# Sorter.net
KiCad netlist of a schematic drawn in EAGLE
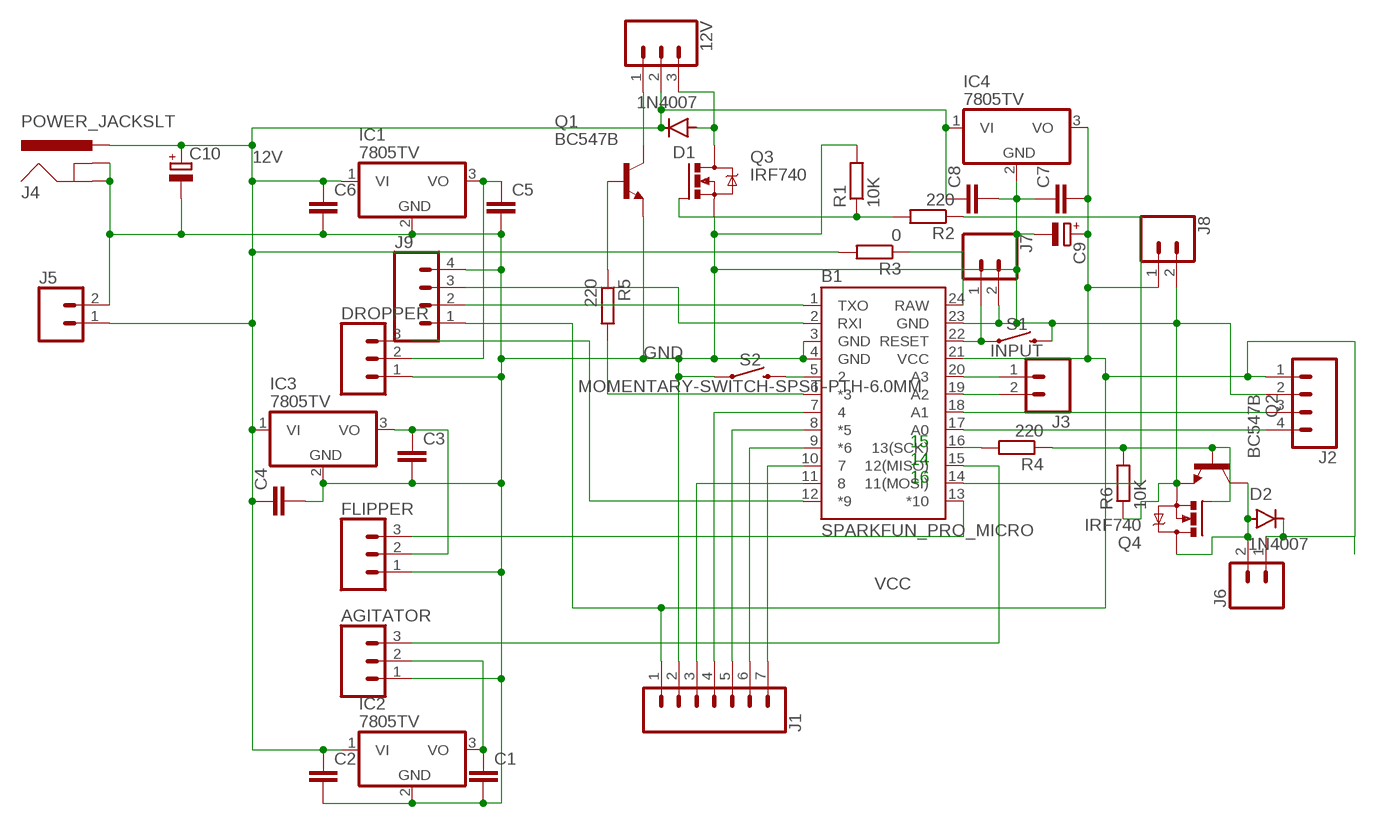
[diagram p0: schematic, sheet 1]

(export (version "E")
  (design (tool "Eeschema 10.0.6"))
  (components
    (comp (ref "12V")
      (value "CONN_03LONGPADS")
      (footprint "eagle-import:1X03_LONGPADS")
      (libsource (lib "eagle-import") (part "CONN_03LONGPADS"))
    )
    (comp (ref "AGITATOR")
      (value "CONN_03LONGPADS")
      (footprint "eagle-import:1X03_LONGPADS")
      (libsource (lib "eagle-import") (part "CONN_03LONGPADS"))
    )
    (comp (ref "B1")
      (value "SPARKFUN_PRO_MICRO")
      (footprint "eagle-import:SPARKFUN_PRO_MICRO")
      (libsource (lib "eagle-import") (part "SPARKFUN_PRO_MICRO"))
    )
    (comp (ref "C1")
      (value "C2.5/2")
      (footprint "eagle-import:C2.5-2")
      (libsource (lib "eagle-import") (part "C2.5/2"))
    )
    (comp (ref "C2")
      (value "C2.5/2")
      (footprint "eagle-import:C2.5-2")
      (libsource (lib "eagle-import") (part "C2.5/2"))
    )
    (comp (ref "C3")
      (value "C2.5/2")
      (footprint "eagle-import:C2.5-2")
      (libsource (lib "eagle-import") (part "C2.5/2"))
    )
    (comp (ref "C4")
      (value "C2.5/2")
      (footprint "eagle-import:C2.5-2")
      (libsource (lib "eagle-import") (part "C2.5/2"))
    )
    (comp (ref "C5")
      (value "C2.5/2")
      (footprint "eagle-import:C2.5-2")
      (libsource (lib "eagle-import") (part "C2.5/2"))
    )
    (comp (ref "C6")
      (value "C2.5/2")
      (footprint "eagle-import:C2.5-2")
      (libsource (lib "eagle-import") (part "C2.5/2"))
    )
    (comp (ref "C7")
      (value "C2.5/2")
      (footprint "eagle-import:C2.5-2")
      (libsource (lib "eagle-import") (part "C2.5/2"))
    )
    (comp (ref "C8")
      (value "C2.5/2")
      (footprint "eagle-import:C2.5-2")
      (libsource (lib "eagle-import") (part "C2.5/2"))
    )
    (comp (ref "C9")
      (value "CPOL-EUE2.5-5")
      (footprint "eagle-import:E2,5-5")
      (libsource (lib "eagle-import") (part "CPOL-EUE2.5-5"))
    )
    (comp (ref "C10")
      (value "CPOL-EUE2.5-5")
      (footprint "eagle-import:E2,5-5")
      (libsource (lib "eagle-import") (part "CPOL-EUE2.5-5"))
    )
    (comp (ref "D1")
      (value "1N4007")
      (footprint "eagle-import:DO-41")
      (fields
        (field (name "DIGIKEY_PART_NUMBER") "1N4007MSCT-ND")
        (field (name "MANUFACTURER") "Micro Commercial Co")
        (field (name "CREATED_BY") "PCBLayout.com")
      )
      (libsource (lib "eagle-import") (part "1N4007"))
    )
    (comp (ref "D2")
      (value "1N4007")
      (footprint "eagle-import:DO-41")
      (fields
        (field (name "DIGIKEY_PART_NUMBER") "1N4007MSCT-ND")
        (field (name "MANUFACTURER") "Micro Commercial Co")
        (field (name "CREATED_BY") "PCBLayout.com")
      )
      (libsource (lib "eagle-import") (part "1N4007"))
    )
    (comp (ref "DROPPER")
      (value "CONN_03LONGPADS")
      (footprint "eagle-import:1X03_LONGPADS")
      (libsource (lib "eagle-import") (part "CONN_03LONGPADS"))
    )
    (comp (ref "FLIPPER")
      (value "CONN_03LONGPADS")
      (footprint "eagle-import:1X03_LONGPADS")
      (libsource (lib "eagle-import") (part "CONN_03LONGPADS"))
    )
    (comp (ref "IC1")
      (value "7805TV")
      (footprint "eagle-import:TO220V")
      (libsource (lib "eagle-import") (part "78TV05"))
    )
    (comp (ref "IC2")
      (value "7805TV")
      (footprint "eagle-import:TO220V")
      (libsource (lib "eagle-import") (part "78TV05"))
    )
    (comp (ref "IC3")
      (value "7805TV")
      (footprint "eagle-import:TO220V")
      (libsource (lib "eagle-import") (part "78TV05"))
    )
    (comp (ref "IC4")
      (value "7805TV")
      (footprint "eagle-import:TO220V")
      (libsource (lib "eagle-import") (part "78TV05"))
    )
    (comp (ref "J1")
      (value "CONN_07LONGPADS")
      (footprint "eagle-import:1X07_LONGPADS")
      (libsource (lib "eagle-import") (part "CONN_07LONGPADS"))
    )
    (comp (ref "J2")
      (value "CONN_04LONGPADS")
      (footprint "eagle-import:1X04_LONGPADS")
      (libsource (lib "eagle-import") (part "CONN_04LONGPADS"))
    )
    (comp (ref "J3")
      (value "CONN_02")
      (footprint "eagle-import:1X02")
      (libsource (lib "eagle-import") (part "CONN_02"))
    )
    (comp (ref "J4")
      (value "POWER_JACKSLT")
      (footprint "eagle-import:POWER_JACK_SLOT")
      (libsource (lib "eagle-import") (part "POWER_JACKSLT"))
    )
    (comp (ref "J5")
      (value "CONN_023.5MM")
      (footprint "eagle-import:SCREWTERMINAL-3.5MM-2")
      (libsource (lib "eagle-import") (part "CONN_023.5MM"))
    )
    (comp (ref "J6")
      (value "CONN_02PTH3")
      (footprint "eagle-import:1X02_LONGPADS")
      (libsource (lib "eagle-import") (part "CONN_02PTH3"))
    )
    (comp (ref "J7")
      (value "CONN_02PTH3")
      (footprint "eagle-import:1X02_LONGPADS")
      (libsource (lib "eagle-import") (part "CONN_02PTH3"))
    )
    (comp (ref "J8")
      (value "CONN_02")
      (footprint "eagle-import:1X02")
      (libsource (lib "eagle-import") (part "CONN_02"))
    )
    (comp (ref "J9")
      (value "CONN_04")
      (footprint "eagle-import:1X04")
      (libsource (lib "eagle-import") (part "CONN_04"))
    )
    (comp (ref "Q1")
      (value "BC547B")
      (footprint "eagle-import:TO92")
      (libsource (lib "eagle-import") (part "BC547B"))
    )
    (comp (ref "Q2")
      (value "BC547B")
      (footprint "eagle-import:TO92")
      (libsource (lib "eagle-import") (part "BC547B"))
    )
    (comp (ref "Q3")
      (value "IRF740")
      (footprint "eagle-import:TO220BV")
      (libsource (lib "eagle-import") (part "IRF740"))
    )
    (comp (ref "Q4")
      (value "IRF740")
      (footprint "eagle-import:TO220BV")
      (libsource (lib "eagle-import") (part "IRF740"))
    )
    (comp (ref "R1")
      (value "10K")
      (footprint "eagle-import:0204_7")
      (libsource (lib "eagle-import") (part "R-EU_0204/7"))
    )
    (comp (ref "R2")
      (value "220")
      (footprint "eagle-import:0204_7")
      (libsource (lib "eagle-import") (part "R-EU_0204/7"))
    )
    (comp (ref "R3")
      (value "0")
      (footprint "eagle-import:0204_7")
      (libsource (lib "eagle-import") (part "R-EU_0204/7"))
    )
    (comp (ref "R4")
      (value "220")
      (footprint "eagle-import:0204_7")
      (libsource (lib "eagle-import") (part "R-EU_0204/7"))
    )
    (comp (ref "R5")
      (value "220")
      (footprint "eagle-import:0204_7")
      (libsource (lib "eagle-import") (part "R-EU_0204/7"))
    )
    (comp (ref "R6")
      (value "10K")
      (footprint "eagle-import:0204_7")
      (libsource (lib "eagle-import") (part "R-EU_0204/7"))
    )
    (comp (ref "S1")
      (value "INPUT")
      (footprint "eagle-import:TACTILE_SWITCH_PTH_6.0MM")
      (libsource (lib "eagle-import") (part "MOMENTARY-SWITCH-SPST-PTH-6.0MM"))
    )
    (comp (ref "S2")
      (value "MOMENTARY-SWITCH-SPST-PTH-6.0MM")
      (footprint "eagle-import:TACTILE_SWITCH_PTH_6.0MM")
      (libsource (lib "eagle-import") (part "MOMENTARY-SWITCH-SPST-PTH-6.0MM"))
    )
  )
  (nets
    (net (code "1") (name "/12V") (class "Default")
      (node (ref "12V") (pin "2") (pinfunction "2_2") (pintype "passive"))
      (node (ref "C10") (pin "+") (pinfunction "+_+") (pintype "passive"))
      (node (ref "C2") (pin "1") (pinfunction "1_1") (pintype "passive"))
      (node (ref "C4") (pin "1") (pinfunction "1_1") (pintype "passive"))
      (node (ref "C6") (pin "1") (pinfunction "1_1") (pintype "passive"))
      (node (ref "C8") (pin "1") (pinfunction "1_1") (pintype "passive"))
      (node (ref "D1") (pin "C") (pinfunction "C_C") (pintype "passive"))
      (node (ref "IC1") (pin "1") (pinfunction "VI_1") (pintype "input"))
      (node (ref "IC2") (pin "1") (pinfunction "VI_1") (pintype "input"))
      (node (ref "IC3") (pin "1") (pinfunction "VI_1") (pintype "input"))
      (node (ref "IC4") (pin "1") (pinfunction "VI_1") (pintype "input"))
      (node (ref "J4") (pin "PWR") (pinfunction "PWR_PWR") (pintype "bidirectional"))
      (node (ref "J5") (pin "1") (pinfunction "1_1") (pintype "passive"))
      (node (ref "R3") (pin "2") (pinfunction "2_2") (pintype "passive"))
    )
    (net (code "2") (name "/GND") (class "Default")
      (node (ref "AGITATOR") (pin "1") (pinfunction "1_1") (pintype "passive"))
      (node (ref "B1") (pin "23") (pinfunction "GND_23") (pintype "power_in"))
      (node (ref "B1") (pin "3") (pinfunction "GND_3") (pintype "power_in"))
      (node (ref "B1") (pin "4") (pinfunction "GND_4") (pintype "power_in"))
      (node (ref "C1") (pin "2") (pinfunction "2_2") (pintype "passive"))
      (node (ref "C10") (pin "-") (pinfunction "-_-") (pintype "passive"))
      (node (ref "C2") (pin "2") (pinfunction "2_2") (pintype "passive"))
      (node (ref "C3") (pin "2") (pinfunction "2_2") (pintype "passive"))
      (node (ref "C4") (pin "2") (pinfunction "2_2") (pintype "passive"))
      (node (ref "C5") (pin "2") (pinfunction "2_2") (pintype "passive"))
      (node (ref "C6") (pin "2") (pinfunction "2_2") (pintype "passive"))
      (node (ref "C7") (pin "1") (pinfunction "1_1") (pintype "passive"))
      (node (ref "C8") (pin "2") (pinfunction "2_2") (pintype "passive"))
      (node (ref "C9") (pin "-") (pinfunction "-_-") (pintype "passive"))
      (node (ref "DROPPER") (pin "1") (pinfunction "1_1") (pintype "passive"))
      (node (ref "FLIPPER") (pin "1") (pinfunction "1_1") (pintype "passive"))
      (node (ref "IC1") (pin "2") (pinfunction "GND_2") (pintype "passive"))
      (node (ref "IC2") (pin "2") (pinfunction "GND_2") (pintype "passive"))
      (node (ref "IC3") (pin "2") (pinfunction "GND_2") (pintype "passive"))
      (node (ref "IC4") (pin "2") (pinfunction "GND_2") (pintype "passive"))
      (node (ref "J1") (pin "2") (pinfunction "2_2") (pintype "passive"))
      (node (ref "J2") (pin "2") (pinfunction "2_2") (pintype "passive"))
      (node (ref "J4") (pin "GND@1") (pinfunction "GNDBREAK_GND@1") (pintype "bidirectional"))
      (node (ref "J4") (pin "GND@2") (pinfunction "GND_GND@2") (pintype "bidirectional"))
      (node (ref "J5") (pin "2") (pinfunction "2_2") (pintype "passive"))
      (node (ref "J7") (pin "2") (pinfunction "2_2") (pintype "passive"))
      (node (ref "J8") (pin "2") (pinfunction "2_2") (pintype "passive"))
      (node (ref "J9") (pin "4") (pinfunction "4_4") (pintype "passive"))
      (node (ref "Q1") (pin "1") (pinfunction "E_1") (pintype "passive"))
      (node (ref "Q2") (pin "1") (pinfunction "E_1") (pintype "passive"))
      (node (ref "Q3") (pin "S") (pinfunction "S_S") (pintype "passive"))
      (node (ref "Q4") (pin "S") (pinfunction "S_S") (pintype "passive"))
      (node (ref "R1") (pin "2") (pinfunction "2_2") (pintype "passive"))
      (node (ref "R6") (pin "1") (pinfunction "1_1") (pintype "passive"))
      (node (ref "S1") (pin "3") (pinfunction "2_3") (pintype "passive"))
      (node (ref "S2") (pin "1") (pinfunction "1_1") (pintype "passive"))
    )
    (net (code "3") (name "/VCC") (class "Default")
      (node (ref "B1") (pin "21") (pinfunction "VCC_21") (pintype "power_in"))
      (node (ref "C7") (pin "2") (pinfunction "2_2") (pintype "passive"))
      (node (ref "C9") (pin "+") (pinfunction "+_+") (pintype "passive"))
      (node (ref "D2") (pin "C") (pinfunction "C_C") (pintype "passive"))
      (node (ref "IC4") (pin "3") (pinfunction "VO_3") (pintype "passive"))
      (node (ref "J1") (pin "1") (pinfunction "1_1") (pintype "passive"))
      (node (ref "J2") (pin "1") (pinfunction "1_1") (pintype "passive"))
      (node (ref "J6") (pin "1") (pinfunction "1_1") (pintype "passive"))
      (node (ref "J8") (pin "1") (pinfunction "1_1") (pintype "passive"))
      (node (ref "J9") (pin "1") (pinfunction "1_1") (pintype "passive"))
    )
    (net (code "4") (name "Net-(12V-Pad3)") (class "Default")
      (node (ref "12V") (pin "3") (pinfunction "3_3") (pintype "passive"))
      (node (ref "D1") (pin "A") (pinfunction "A_A") (pintype "passive"))
      (node (ref "Q3") (pin "D") (pinfunction "D_D") (pintype "passive"))
    )
    (net (code "5") (name "Net-(B1-*3)") (class "Default")
      (node (ref "B1") (pin "6") (pinfunction "*3_6") (pintype "bidirectional"))
      (node (ref "R5") (pin "2") (pinfunction "2_2") (pintype "passive"))
    )
    (net (code "6") (name "Net-(B1-*5)") (class "Default")
      (node (ref "B1") (pin "8") (pinfunction "*5_8") (pintype "bidirectional"))
      (node (ref "J1") (pin "5") (pinfunction "5_5") (pintype "passive"))
    )
    (net (code "7") (name "Net-(B1-*6)") (class "Default")
      (node (ref "B1") (pin "9") (pinfunction "*6_9") (pintype "bidirectional"))
      (node (ref "J1") (pin "6") (pinfunction "6_6") (pintype "passive"))
    )
    (net (code "8") (name "Net-(B1-*9)") (class "Default")
      (node (ref "B1") (pin "12") (pinfunction "*9_12") (pintype "bidirectional"))
      (node (ref "DROPPER") (pin "3") (pinfunction "3_3") (pintype "passive"))
    )
    (net (code "9") (name "Net-(B1-*10)") (class "Default")
      (node (ref "B1") (pin "13") (pinfunction "*10_13") (pintype "bidirectional"))
      (node (ref "FLIPPER") (pin "3") (pinfunction "3_3") (pintype "passive"))
    )
    (net (code "10") (name "Net-(B1-2)") (class "Default")
      (node (ref "B1") (pin "5") (pinfunction "2_5") (pintype "bidirectional"))
      (node (ref "S2") (pin "3") (pinfunction "2_3") (pintype "passive"))
    )
    (net (code "11") (name "Net-(B1-4)") (class "Default")
      (node (ref "B1") (pin "7") (pinfunction "4_7") (pintype "bidirectional"))
      (node (ref "J1") (pin "4") (pinfunction "4_4") (pintype "passive"))
    )
    (net (code "12") (name "Net-(B1-7)") (class "Default")
      (node (ref "B1") (pin "10") (pinfunction "7_10") (pintype "bidirectional"))
      (node (ref "J1") (pin "7") (pinfunction "7_7") (pintype "passive"))
    )
    (net (code "13") (name "Net-(B1-8)") (class "Default")
      (node (ref "B1") (pin "11") (pinfunction "8_11") (pintype "bidirectional"))
      (node (ref "J1") (pin "3") (pinfunction "3_3") (pintype "passive"))
    )
    (net (code "14") (name "Net-(B1-11(MOSI))") (class "Default")
      (node (ref "B1") (pin "14") (pinfunction "11(MOSI)_14") (pintype "bidirectional"))
      (node (ref "R2") (pin "1") (pinfunction "1_1") (pintype "passive"))
    )
    (net (code "15") (name "Net-(B1-12(MISO))") (class "Default")
      (node (ref "AGITATOR") (pin "3") (pinfunction "3_3") (pintype "passive"))
      (node (ref "B1") (pin "15") (pinfunction "12(MISO)_15") (pintype "bidirectional"))
    )
    (net (code "16") (name "Net-(B1-13(SCK))") (class "Default")
      (node (ref "B1") (pin "16") (pinfunction "13(SCK)_16") (pintype "bidirectional"))
      (node (ref "R4") (pin "2") (pinfunction "2_2") (pintype "passive"))
    )
    (net (code "17") (name "Net-(B1-A0)") (class "Default")
      (node (ref "B1") (pin "17") (pinfunction "A0_17") (pintype "bidirectional"))
      (node (ref "J2") (pin "4") (pinfunction "4_4") (pintype "passive"))
    )
    (net (code "18") (name "Net-(B1-A1)") (class "Default")
      (node (ref "B1") (pin "18") (pinfunction "A1_18") (pintype "bidirectional"))
      (node (ref "J2") (pin "3") (pinfunction "3_3") (pintype "passive"))
    )
    (net (code "19") (name "Net-(B1-A2)") (class "Default")
      (node (ref "B1") (pin "19") (pinfunction "A2_19") (pintype "bidirectional"))
      (node (ref "J3") (pin "2") (pinfunction "2_2") (pintype "passive"))
    )
    (net (code "20") (name "Net-(B1-A3)") (class "Default")
      (node (ref "B1") (pin "20") (pinfunction "A3_20") (pintype "bidirectional"))
      (node (ref "J3") (pin "1") (pinfunction "1_1") (pintype "passive"))
    )
    (net (code "21") (name "Net-(B1-RAW)") (class "Default")
      (node (ref "B1") (pin "24") (pinfunction "RAW_24") (pintype "power_in"))
      (node (ref "R3") (pin "1") (pinfunction "1_1") (pintype "passive"))
    )
    (net (code "22") (name "Net-(B1-RESET)") (class "Default")
      (node (ref "B1") (pin "22") (pinfunction "RESET_22") (pintype "bidirectional"))
      (node (ref "J7") (pin "1") (pinfunction "1_1") (pintype "passive"))
      (node (ref "S1") (pin "1") (pinfunction "1_1") (pintype "passive"))
    )
    (net (code "23") (name "Net-(B1-RXI)") (class "Default")
      (node (ref "B1") (pin "2") (pinfunction "RXI_2") (pintype "bidirectional"))
      (node (ref "J9") (pin "3") (pinfunction "3_3") (pintype "passive"))
    )
    (net (code "24") (name "Net-(B1-TXO)") (class "Default")
      (node (ref "B1") (pin "1") (pinfunction "TXO_1") (pintype "bidirectional"))
      (node (ref "J9") (pin "2") (pinfunction "2_2") (pintype "passive"))
    )
    (net (code "25") (name "Net-(IC1-VO)") (class "Default")
      (node (ref "C5") (pin "1") (pinfunction "1_1") (pintype "passive"))
      (node (ref "DROPPER") (pin "2") (pinfunction "2_2") (pintype "passive"))
      (node (ref "IC1") (pin "3") (pinfunction "VO_3") (pintype "passive"))
    )
    (net (code "26") (name "Net-(IC2-VO)") (class "Default")
      (node (ref "AGITATOR") (pin "2") (pinfunction "2_2") (pintype "passive"))
      (node (ref "C1") (pin "1") (pinfunction "1_1") (pintype "passive"))
      (node (ref "IC2") (pin "3") (pinfunction "VO_3") (pintype "passive"))
    )
    (net (code "27") (name "Net-(IC3-VO)") (class "Default")
      (node (ref "C3") (pin "1") (pinfunction "1_1") (pintype "passive"))
      (node (ref "FLIPPER") (pin "2") (pinfunction "2_2") (pintype "passive"))
      (node (ref "IC3") (pin "3") (pinfunction "VO_3") (pintype "passive"))
    )
    (net (code "28") (name "Net-(Q1-B)") (class "Default")
      (node (ref "Q1") (pin "2") (pinfunction "B_2") (pintype "passive"))
      (node (ref "R5") (pin "1") (pinfunction "1_1") (pintype "passive"))
    )
    (net (code "29") (name "Net-(Q1-C)") (class "Default")
      (node (ref "12V") (pin "1") (pinfunction "1_1") (pintype "passive"))
      (node (ref "Q1") (pin "3") (pinfunction "C_3") (pintype "passive"))
    )
    (net (code "30") (name "Net-(Q2-B)") (class "Default")
      (node (ref "Q2") (pin "2") (pinfunction "B_2") (pintype "passive"))
      (node (ref "Q4") (pin "G") (pinfunction "G_G") (pintype "passive"))
      (node (ref "R4") (pin "1") (pinfunction "1_1") (pintype "passive"))
      (node (ref "R6") (pin "2") (pinfunction "2_2") (pintype "passive"))
    )
    (net (code "31") (name "Net-(Q2-C)") (class "Default")
      (node (ref "D2") (pin "A") (pinfunction "A_A") (pintype "passive"))
      (node (ref "J6") (pin "2") (pinfunction "2_2") (pintype "passive"))
      (node (ref "Q2") (pin "3") (pinfunction "C_3") (pintype "passive"))
      (node (ref "Q4") (pin "D") (pinfunction "D_D") (pintype "passive"))
    )
    (net (code "32") (name "Net-(Q3-PadG)") (class "Default")
      (node (ref "Q3") (pin "G") (pinfunction "G_G") (pintype "passive"))
      (node (ref "R1") (pin "1") (pinfunction "1_1") (pintype "passive"))
      (node (ref "R2") (pin "2") (pinfunction "2_2") (pintype "passive"))
    )
  )
)
